# 468172_001_Interface.net
KiCad netlist of a schematic drawn in Altium Designer
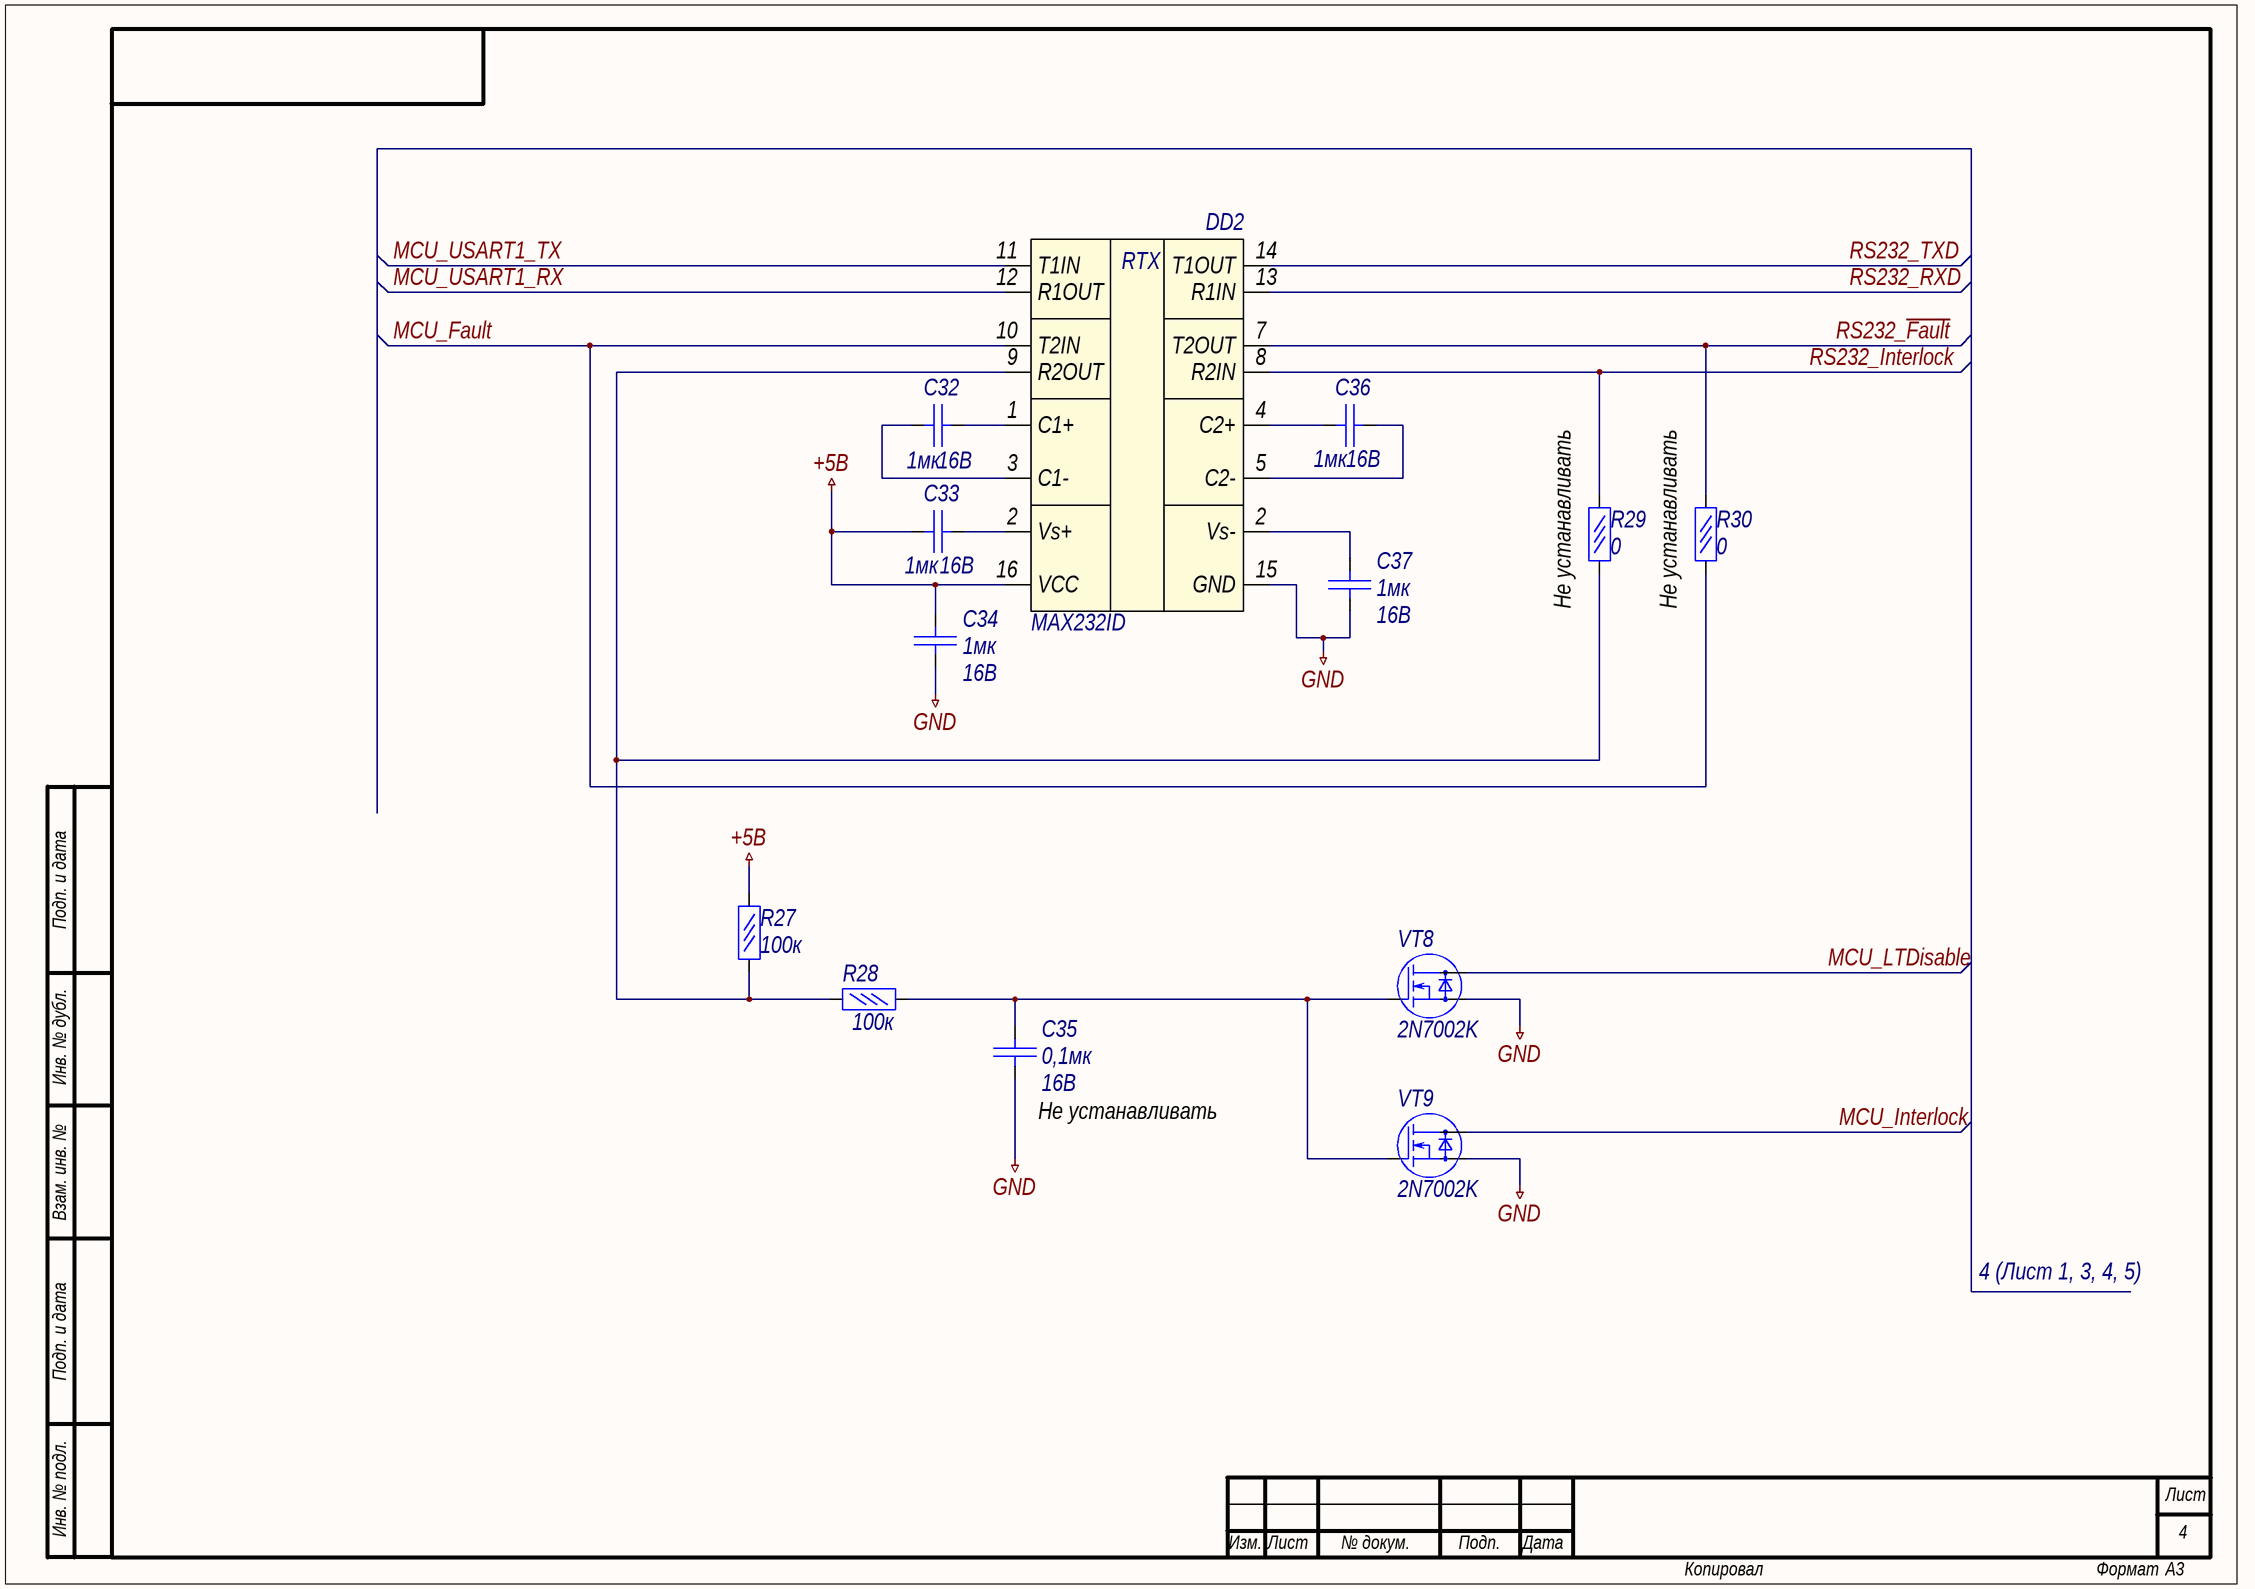
[diagram p0: РЕУН.468172.001_Interface.SchDoc]

(export (version "E")
  (design (tool "Eeschema 10.0.6"))
  (components
    (comp (ref "C32")
      (value "1мк")
      (footprint "C0805_AA")
      (description "Конденсатор кер.")
      (fields (field (name "VOLTAGE") "16В"))
      (libsource (lib "Library_Diana") (part "Конденсатор кер."))
    )
    (comp (ref "C33")
      (value "1мк")
      (footprint "C0805_AA")
      (description "Конденсатор кер.")
      (fields (field (name "VOLTAGE") "16В"))
      (libsource (lib "Library_Diana") (part "Конденсатор кер."))
    )
    (comp (ref "C34")
      (value "1мк")
      (footprint "C0805_AA")
      (description "Конденсатор кер.")
      (fields (field (name "VOLTAGE") "16В"))
      (libsource (lib "Library_Diana") (part "Конденсатор кер."))
    )
    (comp (ref "C35")
      (value "0,1мк")
      (footprint "C0805_AA")
      (description "Конденсатор кер.")
      (fields (field (name "VOLTAGE") "16В"))
      (libsource (lib "Library_Diana") (part "Конденсатор кер."))
    )
    (comp (ref "C36")
      (value "1мк")
      (footprint "C0805_AA")
      (description "Конденсатор кер.")
      (fields (field (name "VOLTAGE") "16В"))
      (libsource (lib "Library_Diana") (part "Конденсатор кер."))
    )
    (comp (ref "C37")
      (value "1мк")
      (footprint "C0805_AA")
      (description "Конденсатор кер.")
      (fields (field (name "VOLTAGE") "16В"))
      (libsource (lib "Library_Diana") (part "Конденсатор кер."))
    )
    (comp (ref "DD2")
      (value "MAX232ID")
      (description "Dual EIA-232 Drivers/Receivers")
      (libsource (lib "Library_Diana") (part "MAX232ID"))
    )
    (comp (ref "R27")
      (value "100к")
      (footprint "R1206")
      (description "Резистор 0,05Вт")
      (libsource (lib "Library_Diana") (part "Резистор  0,05Вт"))
    )
    (comp (ref "R28")
      (value "100к")
      (footprint "R1206")
      (description "Резистор 0,05Вт")
      (libsource (lib "") (part "Резистор  0,05Вт_1"))
    )
    (comp (ref "R29")
      (value "0")
      (footprint "R1206")
      (description "Резистор 0,05Вт")
      (libsource (lib "Library_Diana") (part "Резистор  0,05Вт"))
    )
    (comp (ref "R30")
      (value "0")
      (footprint "R1206")
      (description "Резистор 0,05Вт")
      (libsource (lib "Library_Diana") (part "Резистор  0,05Вт"))
    )
    (comp (ref "VT8")
      (value "2N7002K")
      (footprint "SOT:SOT23-3")
      (fields (field (name "NAME") "2N7002K"))
      (libsource (lib "Library_Diana") (part "mosfet-n"))
    )
    (comp (ref "VT9")
      (value "2N7002K")
      (footprint "SOT:SOT23-3")
      (fields (field (name "NAME") "2N7002K"))
      (libsource (lib "Library_Diana") (part "mosfet-n"))
    )
  )
  (nets
    (net (code "1") (name "+5В") (class "Default")
      (node (ref "C33") (pin "2") (pinfunction "2_2") (pintype "passive"))
      (node (ref "C34") (pin "1") (pinfunction "1_1") (pintype "passive"))
      (node (ref "DD2") (pin "16") (pinfunction "VCC_16") (pintype "passive"))
      (node (ref "R27") (pin "1") (pinfunction "1_1") (pintype "passive"))
    )
    (net (code "2") (name "/MCU_Fault") (class "Default")
      (node (ref "DD2") (pin "10") (pinfunction "T2IN_10") (pintype "passive"))
      (node (ref "R30") (pin "2") (pinfunction "2_2") (pintype "passive"))
    )
    (net (code "3") (name "/MCU_Interlock") (class "Default")
      (node (ref "VT9") (pin "3") (pinfunction "D_3") (pintype "passive"))
    )
    (net (code "4") (name "/MCU_LTDisable") (class "Default")
      (node (ref "VT8") (pin "3") (pinfunction "D_3") (pintype "passive"))
    )
    (net (code "5") (name "/MCU_USART1_RX") (class "Default")
      (node (ref "DD2") (pin "12") (pinfunction "R1OUT_12") (pintype "passive"))
    )
    (net (code "6") (name "/MCU_USART1_TX") (class "Default")
      (node (ref "DD2") (pin "11") (pinfunction "T1IN_11") (pintype "passive"))
    )
    (net (code "7") (name "/RS232_Interlock") (class "Default")
      (node (ref "DD2") (pin "8") (pinfunction "R2IN_8") (pintype "passive"))
      (node (ref "R29") (pin "1") (pinfunction "1_1") (pintype "passive"))
    )
    (net (code "8") (name "/RS232_RXD") (class "Default")
      (node (ref "DD2") (pin "13") (pinfunction "R1IN_13") (pintype "passive"))
    )
    (net (code "9") (name "/RS232_TXD") (class "Default")
      (node (ref "DD2") (pin "14") (pinfunction "T1OUT_14") (pintype "passive"))
    )
    (net (code "10") (name "/RS232_~{Fault}") (class "Default")
      (node (ref "DD2") (pin "7") (pinfunction "T2OUT_7") (pintype "passive"))
      (node (ref "R30") (pin "1") (pinfunction "1_1") (pintype "passive"))
    )
    (net (code "11") (name "GND") (class "Default")
      (node (ref "C34") (pin "2") (pinfunction "2_2") (pintype "passive"))
      (node (ref "C35") (pin "2") (pinfunction "2_2") (pintype "passive"))
      (node (ref "C37") (pin "2") (pinfunction "2_2") (pintype "passive"))
      (node (ref "DD2") (pin "15") (pinfunction "GND_15") (pintype "passive"))
      (node (ref "VT8") (pin "2") (pinfunction "S_2") (pintype "passive"))
      (node (ref "VT9") (pin "2") (pinfunction "S_2") (pintype "passive"))
    )
    (net (code "12") (name "Net-(DD2-C1+)") (class "Default")
      (node (ref "C32") (pin "1") (pinfunction "1_1") (pintype "passive"))
      (node (ref "DD2") (pin "1") (pinfunction "C1+_1") (pintype "passive"))
    )
    (net (code "13") (name "Net-(DD2-C1-)") (class "Default")
      (node (ref "C32") (pin "2") (pinfunction "2_2") (pintype "passive"))
      (node (ref "DD2") (pin "3") (pinfunction "C1-_3") (pintype "passive"))
    )
    (net (code "14") (name "Net-(DD2-C2+)") (class "Default")
      (node (ref "C36") (pin "2") (pinfunction "2_2") (pintype "passive"))
      (node (ref "DD2") (pin "4") (pinfunction "C2+_4") (pintype "passive"))
    )
    (net (code "15") (name "Net-(DD2-C2-)") (class "Default")
      (node (ref "C36") (pin "1") (pinfunction "1_1") (pintype "passive"))
      (node (ref "DD2") (pin "5") (pinfunction "C2-_5") (pintype "passive"))
    )
    (net (code "16") (name "Net-(DD2-R2OUT)") (class "Default")
      (node (ref "DD2") (pin "9") (pinfunction "R2OUT_9") (pintype "passive"))
      (node (ref "R27") (pin "2") (pinfunction "2_2") (pintype "passive"))
      (node (ref "R28") (pin "2") (pinfunction "2_2") (pintype "passive"))
      (node (ref "R29") (pin "2") (pinfunction "2_2") (pintype "passive"))
    )
    (net (code "17") (name "Net-(DD2-Vs+)") (class "Default")
      (node (ref "C33") (pin "1") (pinfunction "1_1") (pintype "passive"))
      (node (ref "DD2") (pin "2") (pinfunction "Vs+_2") (pintype "passive"))
    )
    (net (code "18") (name "Net-(DD2-Vs-)") (class "Default")
      (node (ref "C37") (pin "1") (pinfunction "1_1") (pintype "passive"))
      (node (ref "DD2") (pin "2") (pinfunction "Vs-_2") (pintype "passive"))
    )
    (net (code "19") (name "Net-(VT8-G)") (class "Default")
      (node (ref "C35") (pin "1") (pinfunction "1_1") (pintype "passive"))
      (node (ref "R28") (pin "1") (pinfunction "1_1") (pintype "passive"))
      (node (ref "VT8") (pin "1") (pinfunction "G_1") (pintype "passive"))
      (node (ref "VT9") (pin "1") (pinfunction "G_1") (pintype "passive"))
    )
  )
)
